# lights.net
KiCad netlist of a schematic drawn in Altium Designer
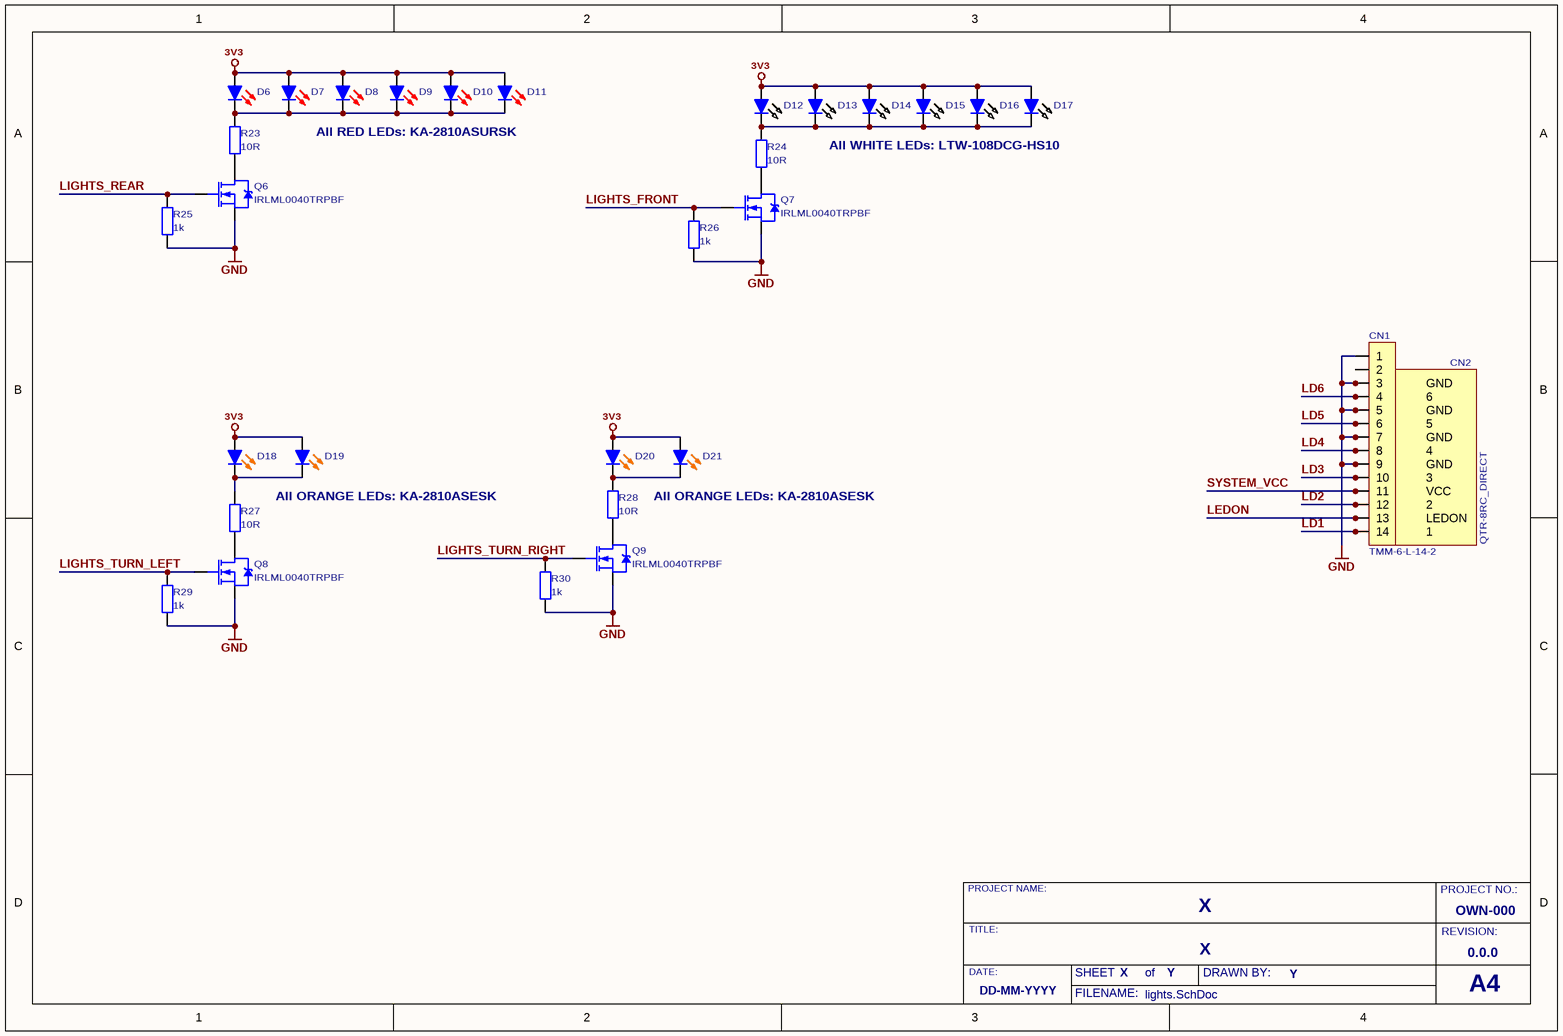
[diagram p0: lights.SchDoc]

(export (version "E")
  (design (tool "Eeschema 10.0.6"))
  (components
    (comp (ref "CN1")
      (value "TMM-6-L-14-2")
      (footprint "MM_14_SMD_LCK")
      (description "14-pin MicroMarch Female Socket With Locking Mechanism, Vertical, SMD")
      (libsource (lib "micromatch") (part "TMM-6-L-14-2"))
    )
    (comp (ref "CN2")
      (value "QTR-8RC_DIRECT")
      (footprint "QTR-8RC_SNAPPED_GOLDPIN_VERTICAL")
      (description "QTR-8RC Reflectance Sensor Array (Pololu item No. 961)")
      (libsource (lib "other_modules") (part "QTR-8RC_DIRECT"))
    )
    (comp (ref "D6")
      (value "KA-2810ASURSK")
      (footprint "LED2810")
      (libsource (lib "leds") (part "KA-2810ASURSK"))
    )
    (comp (ref "D7")
      (value "KA-2810ASURSK")
      (footprint "LED2810")
      (libsource (lib "leds") (part "KA-2810ASURSK"))
    )
    (comp (ref "D8")
      (value "KA-2810ASURSK")
      (footprint "LED2810")
      (libsource (lib "leds") (part "KA-2810ASURSK"))
    )
    (comp (ref "D9")
      (value "KA-2810ASURSK")
      (footprint "LED2810")
      (libsource (lib "leds") (part "KA-2810ASURSK"))
    )
    (comp (ref "D10")
      (value "KA-2810ASURSK")
      (footprint "LED2810")
      (libsource (lib "leds") (part "KA-2810ASURSK"))
    )
    (comp (ref "D11")
      (value "KA-2810ASURSK")
      (footprint "LED2810")
      (libsource (lib "leds") (part "KA-2810ASURSK"))
    )
    (comp (ref "D12")
      (value "LTW-108DCG-HS10")
      (footprint "LED2810")
      (libsource (lib "leds") (part "LTW-108DCG-HS10"))
    )
    (comp (ref "D13")
      (value "LTW-108DCG-HS10")
      (footprint "LED2810")
      (libsource (lib "leds") (part "LTW-108DCG-HS10"))
    )
    (comp (ref "D14")
      (value "LTW-108DCG-HS10")
      (footprint "LED2810")
      (libsource (lib "leds") (part "LTW-108DCG-HS10"))
    )
    (comp (ref "D15")
      (value "LTW-108DCG-HS10")
      (footprint "LED2810")
      (libsource (lib "leds") (part "LTW-108DCG-HS10"))
    )
    (comp (ref "D16")
      (value "LTW-108DCG-HS10")
      (footprint "LED2810")
      (libsource (lib "leds") (part "LTW-108DCG-HS10"))
    )
    (comp (ref "D17")
      (value "LTW-108DCG-HS10")
      (footprint "LED2810")
      (libsource (lib "leds") (part "LTW-108DCG-HS10"))
    )
    (comp (ref "D18")
      (value "KA-2810ASESK")
      (footprint "LED2810")
      (libsource (lib "leds") (part "KA-2810ASESK"))
    )
    (comp (ref "D19")
      (value "KA-2810ASESK")
      (footprint "LED2810")
      (libsource (lib "leds") (part "KA-2810ASESK"))
    )
    (comp (ref "D20")
      (value "KA-2810ASESK")
      (footprint "LED2810")
      (libsource (lib "leds") (part "KA-2810ASESK"))
    )
    (comp (ref "D21")
      (value "KA-2810ASESK")
      (footprint "LED2810")
      (libsource (lib "leds") (part "KA-2810ASESK"))
    )
    (comp (ref "Q6")
      (value "IRLML0040TRPBF")
      (footprint "SOT-23")
      (description "N-Channel; 40V, 3.6A, 1,25W; HEXFET Power MOS-FET")
      (libsource (lib "transistors_mos") (part "IRLML0040TRPBF"))
    )
    (comp (ref "Q7")
      (value "IRLML0040TRPBF")
      (footprint "SOT-23")
      (description "N-Channel; 40V, 3.6A, 1,25W; HEXFET Power MOS-FET")
      (libsource (lib "transistors_mos") (part "IRLML0040TRPBF"))
    )
    (comp (ref "Q8")
      (value "IRLML0040TRPBF")
      (footprint "SOT-23")
      (description "N-Channel; 40V, 3.6A, 1,25W; HEXFET Power MOS-FET")
      (libsource (lib "transistors_mos") (part "IRLML0040TRPBF"))
    )
    (comp (ref "Q9")
      (value "IRLML0040TRPBF")
      (footprint "SOT-23")
      (description "N-Channel; 40V, 3.6A, 1,25W; HEXFET Power MOS-FET")
      (libsource (lib "transistors_mos") (part "IRLML0040TRPBF"))
    )
    (comp (ref "R23")
      (value "10R")
      (footprint "R0805")
      (description "Resistor")
      (libsource (lib "resistors") (part "Res"))
    )
    (comp (ref "R24")
      (value "10R")
      (footprint "R0805")
      (description "Resistor")
      (libsource (lib "resistors") (part "Res"))
    )
    (comp (ref "R25")
      (value "1k")
      (footprint "R0805")
      (description "Resistor")
      (libsource (lib "resistors") (part "Res"))
    )
    (comp (ref "R26")
      (value "1k")
      (footprint "R0805")
      (description "Resistor")
      (libsource (lib "resistors") (part "Res"))
    )
    (comp (ref "R27")
      (value "10R")
      (footprint "R0805")
      (description "Resistor")
      (libsource (lib "resistors") (part "Res"))
    )
    (comp (ref "R28")
      (value "10R")
      (footprint "R0805")
      (description "Resistor")
      (libsource (lib "resistors") (part "Res"))
    )
    (comp (ref "R29")
      (value "1k")
      (footprint "R0805")
      (description "Resistor")
      (libsource (lib "resistors") (part "Res"))
    )
    (comp (ref "R30")
      (value "1k")
      (footprint "R0805")
      (description "Resistor")
      (libsource (lib "resistors") (part "Res"))
    )
  )
  (nets
    (net (code "1") (name "/LD1") (class "Default")
      (node (ref "CN1") (pin "14") (pinfunction "14_14") (pintype "passive"))
      (node (ref "CN2") (pin "1") (pinfunction "1_1") (pintype "passive"))
    )
    (net (code "2") (name "/LD2") (class "Default")
      (node (ref "CN1") (pin "12") (pinfunction "12_12") (pintype "passive"))
      (node (ref "CN2") (pin "2") (pinfunction "2_2") (pintype "passive"))
    )
    (net (code "3") (name "/LD3") (class "Default")
      (node (ref "CN1") (pin "10") (pinfunction "10_10") (pintype "passive"))
      (node (ref "CN2") (pin "3") (pinfunction "3_3") (pintype "passive"))
    )
    (net (code "4") (name "/LD4") (class "Default")
      (node (ref "CN1") (pin "8") (pinfunction "8_8") (pintype "passive"))
      (node (ref "CN2") (pin "4") (pinfunction "4_4") (pintype "passive"))
    )
    (net (code "5") (name "/LD5") (class "Default")
      (node (ref "CN1") (pin "6") (pinfunction "6_6") (pintype "passive"))
      (node (ref "CN2") (pin "5") (pinfunction "5_5") (pintype "passive"))
    )
    (net (code "6") (name "/LD6") (class "Default")
      (node (ref "CN1") (pin "4") (pinfunction "4_4") (pintype "passive"))
      (node (ref "CN2") (pin "6") (pinfunction "6_6") (pintype "passive"))
    )
    (net (code "7") (name "/LEDON") (class "Default")
      (node (ref "CN1") (pin "13") (pinfunction "13_13") (pintype "passive"))
      (node (ref "CN2") (pin "LEDON") (pinfunction "LEDON_LEDON") (pintype "passive"))
    )
    (net (code "8") (name "/LIGHTS_FRONT") (class "Default")
      (node (ref "Q7") (pin "1") (pinfunction "G_1") (pintype "passive"))
      (node (ref "R26") (pin "1") (pinfunction "1_1") (pintype "passive"))
    )
    (net (code "9") (name "/LIGHTS_REAR") (class "Default")
      (node (ref "Q6") (pin "1") (pinfunction "G_1") (pintype "passive"))
      (node (ref "R25") (pin "1") (pinfunction "1_1") (pintype "passive"))
    )
    (net (code "10") (name "/LIGHTS_TURN_LEFT") (class "Default")
      (node (ref "Q8") (pin "1") (pinfunction "G_1") (pintype "passive"))
      (node (ref "R29") (pin "1") (pinfunction "1_1") (pintype "passive"))
    )
    (net (code "11") (name "/LIGHTS_TURN_RIGHT") (class "Default")
      (node (ref "Q9") (pin "1") (pinfunction "G_1") (pintype "passive"))
      (node (ref "R30") (pin "1") (pinfunction "1_1") (pintype "passive"))
    )
    (net (code "12") (name "/SYSTEM_VCC") (class "Default")
      (node (ref "CN1") (pin "11") (pinfunction "11_11") (pintype "passive"))
      (node (ref "CN2") (pin "VCC") (pinfunction "VCC_VCC") (pintype "passive"))
    )
    (net (code "13") (name "3V3") (class "Default")
      (node (ref "D10") (pin "2") (pinfunction "A_2") (pintype "passive"))
      (node (ref "D11") (pin "2") (pinfunction "A_2") (pintype "passive"))
      (node (ref "D12") (pin "2") (pinfunction "A_2") (pintype "passive"))
      (node (ref "D13") (pin "2") (pinfunction "A_2") (pintype "passive"))
      (node (ref "D14") (pin "2") (pinfunction "A_2") (pintype "passive"))
      (node (ref "D15") (pin "2") (pinfunction "A_2") (pintype "passive"))
      (node (ref "D16") (pin "2") (pinfunction "A_2") (pintype "passive"))
      (node (ref "D17") (pin "2") (pinfunction "A_2") (pintype "passive"))
      (node (ref "D18") (pin "2") (pinfunction "A_2") (pintype "passive"))
      (node (ref "D19") (pin "2") (pinfunction "A_2") (pintype "passive"))
      (node (ref "D20") (pin "2") (pinfunction "A_2") (pintype "passive"))
      (node (ref "D21") (pin "2") (pinfunction "A_2") (pintype "passive"))
      (node (ref "D6") (pin "2") (pinfunction "A_2") (pintype "passive"))
      (node (ref "D7") (pin "2") (pinfunction "A_2") (pintype "passive"))
      (node (ref "D8") (pin "2") (pinfunction "A_2") (pintype "passive"))
      (node (ref "D9") (pin "2") (pinfunction "A_2") (pintype "passive"))
    )
    (net (code "14") (name "GND") (class "Default")
      (node (ref "CN1") (pin "1") (pinfunction "1_1") (pintype "passive"))
      (node (ref "CN1") (pin "3") (pinfunction "3_3") (pintype "passive"))
      (node (ref "CN1") (pin "5") (pinfunction "5_5") (pintype "passive"))
      (node (ref "CN1") (pin "7") (pinfunction "7_7") (pintype "passive"))
      (node (ref "CN1") (pin "9") (pinfunction "9_9") (pintype "passive"))
      (node (ref "CN2") (pin "GND") (pinfunction "GND_GND") (pintype "passive"))
      (node (ref "Q6") (pin "2") (pinfunction "S_2") (pintype "passive"))
      (node (ref "Q7") (pin "2") (pinfunction "S_2") (pintype "passive"))
      (node (ref "Q8") (pin "2") (pinfunction "S_2") (pintype "passive"))
      (node (ref "Q9") (pin "2") (pinfunction "S_2") (pintype "passive"))
      (node (ref "R25") (pin "2") (pinfunction "2_2") (pintype "passive"))
      (node (ref "R26") (pin "2") (pinfunction "2_2") (pintype "passive"))
      (node (ref "R29") (pin "2") (pinfunction "2_2") (pintype "passive"))
      (node (ref "R30") (pin "2") (pinfunction "2_2") (pintype "passive"))
    )
    (net (code "15") (name "Net-(D10-K)") (class "Default")
      (node (ref "D10") (pin "1") (pinfunction "K_1") (pintype "passive"))
      (node (ref "D11") (pin "1") (pinfunction "K_1") (pintype "passive"))
      (node (ref "D6") (pin "1") (pinfunction "K_1") (pintype "passive"))
      (node (ref "D7") (pin "1") (pinfunction "K_1") (pintype "passive"))
      (node (ref "D8") (pin "1") (pinfunction "K_1") (pintype "passive"))
      (node (ref "D9") (pin "1") (pinfunction "K_1") (pintype "passive"))
      (node (ref "R23") (pin "1") (pinfunction "1_1") (pintype "passive"))
    )
    (net (code "16") (name "Net-(D12-K)") (class "Default")
      (node (ref "D12") (pin "1") (pinfunction "K_1") (pintype "passive"))
      (node (ref "D13") (pin "1") (pinfunction "K_1") (pintype "passive"))
      (node (ref "D14") (pin "1") (pinfunction "K_1") (pintype "passive"))
      (node (ref "D15") (pin "1") (pinfunction "K_1") (pintype "passive"))
      (node (ref "D16") (pin "1") (pinfunction "K_1") (pintype "passive"))
      (node (ref "D17") (pin "1") (pinfunction "K_1") (pintype "passive"))
      (node (ref "R24") (pin "1") (pinfunction "1_1") (pintype "passive"))
    )
    (net (code "17") (name "Net-(D18-K)") (class "Default")
      (node (ref "D18") (pin "1") (pinfunction "K_1") (pintype "passive"))
      (node (ref "D19") (pin "1") (pinfunction "K_1") (pintype "passive"))
      (node (ref "R27") (pin "1") (pinfunction "1_1") (pintype "passive"))
    )
    (net (code "18") (name "Net-(D20-K)") (class "Default")
      (node (ref "D20") (pin "1") (pinfunction "K_1") (pintype "passive"))
      (node (ref "D21") (pin "1") (pinfunction "K_1") (pintype "passive"))
      (node (ref "R28") (pin "1") (pinfunction "1_1") (pintype "passive"))
    )
    (net (code "19") (name "Net-(Q6-D)") (class "Default")
      (node (ref "Q6") (pin "3") (pinfunction "D_3") (pintype "passive"))
      (node (ref "R23") (pin "2") (pinfunction "2_2") (pintype "passive"))
    )
    (net (code "20") (name "Net-(Q7-D)") (class "Default")
      (node (ref "Q7") (pin "3") (pinfunction "D_3") (pintype "passive"))
      (node (ref "R24") (pin "2") (pinfunction "2_2") (pintype "passive"))
    )
    (net (code "21") (name "Net-(Q8-D)") (class "Default")
      (node (ref "Q8") (pin "3") (pinfunction "D_3") (pintype "passive"))
      (node (ref "R27") (pin "2") (pinfunction "2_2") (pintype "passive"))
    )
    (net (code "22") (name "Net-(Q9-D)") (class "Default")
      (node (ref "Q9") (pin "3") (pinfunction "D_3") (pintype "passive"))
      (node (ref "R28") (pin "2") (pinfunction "2_2") (pintype "passive"))
    )
    (net (code "23") (name "unconnected-(CN1-Pad2)") (class "Default")
      (node (ref "CN1") (pin "2") (pinfunction "2_2") (pintype "passive"))
    )
  )
)
